# AD2.net
KiCad netlist of a schematic drawn in EAGLE
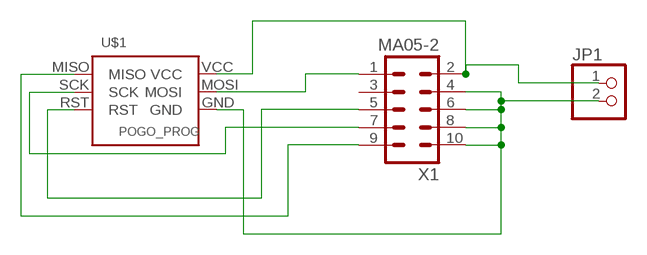
[diagram p0: schematic, sheet 1]

(export (version "E")
  (design (tool "Eeschema 10.0.6"))
  (components
    (comp (ref "JP1")
      (value "PINHD-1X2/90")
      (footprint "eagle-import:1X02_90")
      (libsource (lib "eagle-import") (part "PINHD-1X2/90"))
    )
    (comp (ref "U$1")
      (value "POGO_PROG")
      (footprint "eagle-import:POGO_PROG")
      (libsource (lib "eagle-import") (part "POGO_PROG"))
    )
    (comp (ref "X1")
      (value "MA05-2")
      (footprint "eagle-import:MA05-2")
      (libsource (lib "eagle-import") (part "MA05-2"))
    )
  )
  (nets
    (net (code "1") (name "Net-(JP1-Pad1)") (class "Default")
      (node (ref "JP1") (pin "1") (pinfunction "1_1") (pintype "passive"))
      (node (ref "U$1") (pin "VCC") (pinfunction "VCC_VCC") (pintype "bidirectional"))
      (node (ref "X1") (pin "2") (pinfunction "2_2") (pintype "passive"))
    )
    (net (code "2") (name "Net-(JP1-Pad2)") (class "Default")
      (node (ref "JP1") (pin "2") (pinfunction "2_2") (pintype "passive"))
      (node (ref "U$1") (pin "GND") (pinfunction "GND_GND") (pintype "power_in"))
      (node (ref "X1") (pin "10") (pinfunction "10_10") (pintype "passive"))
      (node (ref "X1") (pin "4") (pinfunction "4_4") (pintype "passive"))
      (node (ref "X1") (pin "6") (pinfunction "6_6") (pintype "passive"))
      (node (ref "X1") (pin "8") (pinfunction "8_8") (pintype "passive"))
    )
    (net (code "3") (name "Net-(U$1-PadMISO)") (class "Default")
      (node (ref "U$1") (pin "MISO") (pinfunction "MISO_MISO") (pintype "bidirectional"))
      (node (ref "X1") (pin "9") (pinfunction "9_9") (pintype "passive"))
    )
    (net (code "4") (name "Net-(U$1-PadMOSI)") (class "Default")
      (node (ref "U$1") (pin "MOSI") (pinfunction "MOSI_MOSI") (pintype "bidirectional"))
      (node (ref "X1") (pin "1") (pinfunction "1_1") (pintype "passive"))
    )
    (net (code "5") (name "Net-(U$1-PadRST)") (class "Default")
      (node (ref "U$1") (pin "RST") (pinfunction "RST_RST") (pintype "bidirectional"))
      (node (ref "X1") (pin "5") (pinfunction "5_5") (pintype "passive"))
    )
    (net (code "6") (name "Net-(U$1-PadSCK)") (class "Default")
      (node (ref "U$1") (pin "SCK") (pinfunction "SCK_SCK") (pintype "bidirectional"))
      (node (ref "X1") (pin "7") (pinfunction "7_7") (pintype "passive"))
    )
    (net (code "7") (name "unconnected-(X1-Pad3)") (class "Default")
      (node (ref "X1") (pin "3") (pinfunction "3_3") (pintype "passive"))
    )
  )
)
